# hand_foot_forearm_leg_LED_stemma.net
KiCad netlist of a schematic drawn in EAGLE
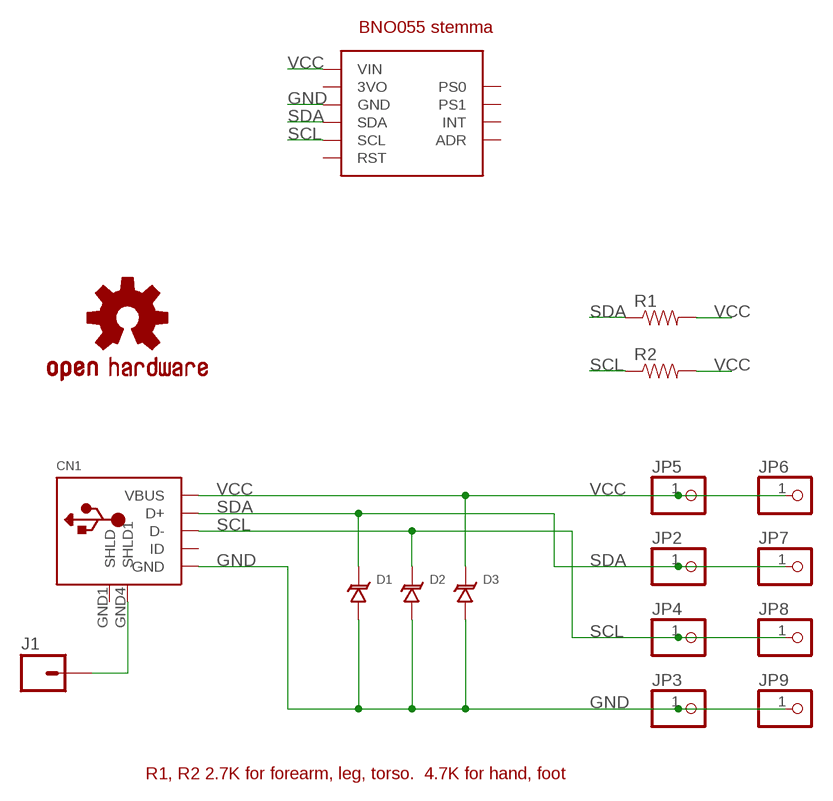
[diagram p0: schematic, sheet 1]

(export (version "E")
  (design (tool "Eeschema 10.0.6"))
  (components
    (comp (ref "CN1")
      (value "USB")
      (footprint "eagle-import:USB-MINIB-THM-MOLEX_NOSLK")
      (libsource (lib "eagle-import") (part "USB"))
    )
    (comp (ref "D1")
      (value "TVS_DIODE_SOD723")
      (footprint "eagle-import:SOD723")
      (libsource (lib "eagle-import") (part "TVS_DIODE_SOD723"))
    )
    (comp (ref "D2")
      (value "TVS_DIODE_SOD723")
      (footprint "eagle-import:SOD723")
      (libsource (lib "eagle-import") (part "TVS_DIODE_SOD723"))
    )
    (comp (ref "D3")
      (value "TVS_DIODE_SOD723")
      (footprint "eagle-import:SOD723")
      (libsource (lib "eagle-import") (part "TVS_DIODE_SOD723"))
    )
    (comp (ref "J1")
      (value "M01PTH")
      (footprint "eagle-import:1X01")
      (libsource (lib "eagle-import") (part "M01PTH"))
    )
    (comp (ref "JP2")
      (value "PINHD-1X1CB")
      (footprint "eagle-import:1X01-CLEANBIG")
      (libsource (lib "eagle-import") (part "PINHD-1X1CB"))
    )
    (comp (ref "JP3")
      (value "PINHD-1X1CB")
      (footprint "eagle-import:1X01-CLEANBIG")
      (libsource (lib "eagle-import") (part "PINHD-1X1CB"))
    )
    (comp (ref "JP4")
      (value "PINHD-1X1CB")
      (footprint "eagle-import:1X01-CLEANBIG")
      (libsource (lib "eagle-import") (part "PINHD-1X1CB"))
    )
    (comp (ref "JP5")
      (value "PINHD-1X1CB")
      (footprint "eagle-import:1X01-CLEANBIG")
      (libsource (lib "eagle-import") (part "PINHD-1X1CB"))
    )
    (comp (ref "JP6")
      (value "PINHD-1X1CB")
      (footprint "eagle-import:1X01-CLEANBIG")
      (libsource (lib "eagle-import") (part "PINHD-1X1CB"))
    )
    (comp (ref "JP7")
      (value "PINHD-1X1CB")
      (footprint "eagle-import:1X01-CLEANBIG")
      (libsource (lib "eagle-import") (part "PINHD-1X1CB"))
    )
    (comp (ref "JP8")
      (value "PINHD-1X1CB")
      (footprint "eagle-import:1X01-CLEANBIG")
      (libsource (lib "eagle-import") (part "PINHD-1X1CB"))
    )
    (comp (ref "JP9")
      (value "PINHD-1X1CB")
      (footprint "eagle-import:1X01-CLEANBIG")
      (libsource (lib "eagle-import") (part "PINHD-1X1CB"))
    )
    (comp (ref "LOGO1")
      (value "OSHW-LOGOS")
      (footprint "eagle-import:OSHW-LOGO-S")
      (libsource (lib "eagle-import") (part "OSHW-LOGOS"))
    )
    (comp (ref "R1")
      (value "RESISTORAXIAL-0.3")
      (footprint "eagle-import:AXIAL-0.3")
      (libsource (lib "eagle-import") (part "RESISTORAXIAL-0.3"))
    )
    (comp (ref "R2")
      (value "RESISTORAXIAL-0.3")
      (footprint "eagle-import:AXIAL-0.3")
      (libsource (lib "eagle-import") (part "RESISTORAXIAL-0.3"))
    )
    (comp (ref "U$2")
      (value "BNO_055_STEMMA")
      (footprint "eagle-import:BNO_STEMMA")
      (libsource (lib "eagle-import") (part "BNO_055_STEMMA"))
    )
  )
  (nets
    (net (code "1") (name "/GND") (class "Default")
      (node (ref "CN1") (pin "GND") (pinfunction "GND_GND") (pintype "power_in"))
      (node (ref "D1") (pin "A") (pinfunction "A_A") (pintype "passive"))
      (node (ref "D2") (pin "A") (pinfunction "A_A") (pintype "passive"))
      (node (ref "D3") (pin "A") (pinfunction "A_A") (pintype "passive"))
      (node (ref "JP3") (pin "1") (pinfunction "1_1") (pintype "passive"))
      (node (ref "JP9") (pin "1") (pinfunction "1_1") (pintype "passive"))
      (node (ref "U$2") (pin "GND") (pinfunction "GND_GND") (pintype "bidirectional"))
    )
    (net (code "2") (name "/SCL") (class "Default")
      (node (ref "CN1") (pin "D-") (pinfunction "D-_D-") (pintype "bidirectional"))
      (node (ref "D2") (pin "C") (pinfunction "C_C") (pintype "passive"))
      (node (ref "JP4") (pin "1") (pinfunction "1_1") (pintype "passive"))
      (node (ref "JP8") (pin "1") (pinfunction "1_1") (pintype "passive"))
      (node (ref "R2") (pin "P$1") (pinfunction "1_P$1") (pintype "passive"))
      (node (ref "U$2") (pin "SCL") (pinfunction "SCL_SCL") (pintype "bidirectional"))
    )
    (net (code "3") (name "/SDA") (class "Default")
      (node (ref "CN1") (pin "D+") (pinfunction "D+_D+") (pintype "bidirectional"))
      (node (ref "D1") (pin "C") (pinfunction "C_C") (pintype "passive"))
      (node (ref "JP2") (pin "1") (pinfunction "1_1") (pintype "passive"))
      (node (ref "JP7") (pin "1") (pinfunction "1_1") (pintype "passive"))
      (node (ref "R1") (pin "P$1") (pinfunction "1_P$1") (pintype "passive"))
      (node (ref "U$2") (pin "SDA") (pinfunction "SDA_SDA") (pintype "bidirectional"))
    )
    (net (code "4") (name "/VCC") (class "Default")
      (node (ref "CN1") (pin "VBUS") (pinfunction "VBUS_VBUS") (pintype "power_in"))
      (node (ref "D3") (pin "C") (pinfunction "C_C") (pintype "passive"))
      (node (ref "JP5") (pin "1") (pinfunction "1_1") (pintype "passive"))
      (node (ref "JP6") (pin "1") (pinfunction "1_1") (pintype "passive"))
      (node (ref "R1") (pin "P$2") (pinfunction "2_P$2") (pintype "passive"))
      (node (ref "R2") (pin "P$2") (pinfunction "2_P$2") (pintype "passive"))
      (node (ref "U$2") (pin "VIN") (pinfunction "VIN_VIN") (pintype "bidirectional"))
    )
    (net (code "5") (name "Net-(CN1-SHLD1)") (class "Default")
      (node (ref "CN1") (pin "GND4") (pinfunction "SHLD1_GND4") (pintype "bidirectional"))
      (node (ref "J1") (pin "1") (pinfunction "1_1") (pintype "passive"))
    )
    (net (code "6") (name "unconnected-(CN1-PadID)") (class "Default")
      (node (ref "CN1") (pin "ID") (pinfunction "ID_ID") (pintype "bidirectional"))
    )
    (net (code "7") (name "unconnected-(CN1-SHLD-PadGND1)") (class "Default")
      (node (ref "CN1") (pin "GND1") (pinfunction "SHLD_GND1") (pintype "bidirectional"))
    )
    (net (code "8") (name "unconnected-(U$2-Pad3VO)") (class "Default")
      (node (ref "U$2") (pin "3VO") (pinfunction "3VO_3VO") (pintype "bidirectional"))
    )
    (net (code "9") (name "unconnected-(U$2-PadADR)") (class "Default")
      (node (ref "U$2") (pin "ADR") (pinfunction "ADR_ADR") (pintype "bidirectional"))
    )
    (net (code "10") (name "unconnected-(U$2-PadINT)") (class "Default")
      (node (ref "U$2") (pin "INT") (pinfunction "INT_INT") (pintype "bidirectional"))
    )
    (net (code "11") (name "unconnected-(U$2-PadPS0)") (class "Default")
      (node (ref "U$2") (pin "PS0") (pinfunction "PS0_PS0") (pintype "bidirectional"))
    )
    (net (code "12") (name "unconnected-(U$2-PadPS1)") (class "Default")
      (node (ref "U$2") (pin "PS1") (pinfunction "PS1_PS1") (pintype "bidirectional"))
    )
    (net (code "13") (name "unconnected-(U$2-PadRST)") (class "Default")
      (node (ref "U$2") (pin "RST") (pinfunction "RST_RST") (pintype "bidirectional"))
    )
  )
)
